# adcsd_shield.net
KiCad netlist of a schematic drawn in EAGLE
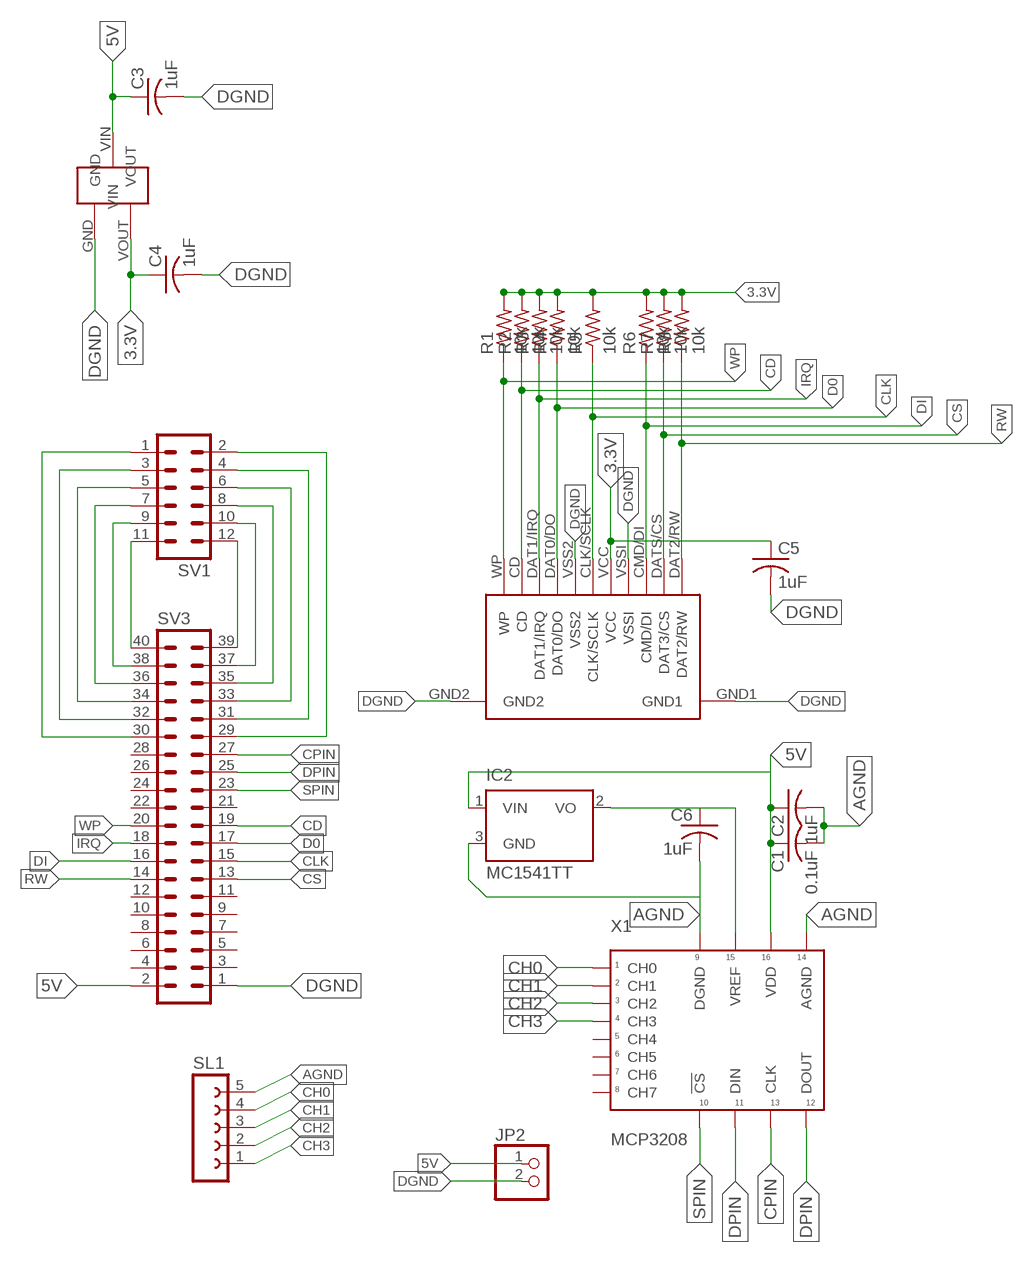
[diagram p0: schematic, sheet 1]

(export (version "E")
  (design (tool "Eeschema 10.0.6"))
  (components
    (comp (ref "C1")
      (value "0.1uF")
      (footprint "eagle-import:C0402")
      (libsource (lib "eagle-import") (part "C-USC0402"))
    )
    (comp (ref "C2")
      (value "1uF")
      (footprint "eagle-import:C0402")
      (libsource (lib "eagle-import") (part "C-USC0402"))
    )
    (comp (ref "C3")
      (value "1uF")
      (footprint "eagle-import:C0402")
      (libsource (lib "eagle-import") (part "C-USC0402"))
    )
    (comp (ref "C4")
      (value "1uF")
      (footprint "eagle-import:C0402")
      (libsource (lib "eagle-import") (part "C-USC0402"))
    )
    (comp (ref "C5")
      (value "1uF")
      (footprint "eagle-import:C0402")
      (libsource (lib "eagle-import") (part "C-USC0402"))
    )
    (comp (ref "C6")
      (value "1uF")
      (footprint "eagle-import:C0402")
      (libsource (lib "eagle-import") (part "C-USC0402"))
    )
    (comp (ref "IC2")
      (value "MC1541TT")
      (footprint "eagle-import:SOT23")
      (libsource (lib "eagle-import") (part "MC15TT41"))
    )
    (comp (ref "JP2")
      (value "PINHD-1X2")
      (footprint "eagle-import:1X02")
      (libsource (lib "eagle-import") (part "PINHD-1X2"))
    )
    (comp (ref "R1")
      (value "10k")
      (footprint "eagle-import:R0603")
      (libsource (lib "eagle-import") (part "R-US_R0603"))
    )
    (comp (ref "R2")
      (value "10k")
      (footprint "eagle-import:R0603")
      (libsource (lib "eagle-import") (part "R-US_R0603"))
    )
    (comp (ref "R3")
      (value "10k")
      (footprint "eagle-import:R0603")
      (libsource (lib "eagle-import") (part "R-US_R0603"))
    )
    (comp (ref "R4")
      (value "10k")
      (footprint "eagle-import:R0603")
      (libsource (lib "eagle-import") (part "R-US_R0603"))
    )
    (comp (ref "R5")
      (value "10k")
      (footprint "eagle-import:R0603")
      (libsource (lib "eagle-import") (part "R-US_R0603"))
    )
    (comp (ref "R6")
      (value "10k")
      (footprint "eagle-import:R0603")
      (libsource (lib "eagle-import") (part "R-US_R0603"))
    )
    (comp (ref "R7")
      (value "10k")
      (footprint "eagle-import:R0603")
      (libsource (lib "eagle-import") (part "R-US_R0603"))
    )
    (comp (ref "R8")
      (value "10k")
      (footprint "eagle-import:R0603")
      (libsource (lib "eagle-import") (part "R-US_R0603"))
    )
    (comp (ref "SL1")
      (value "FE05-1")
      (footprint "eagle-import:FE05-1")
      (libsource (lib "eagle-import") (part "FE05-1"))
    )
    (comp (ref "SV1")
      (value "MA06-2")
      (footprint "eagle-import:MA06-2")
      (libsource (lib "eagle-import") (part "MA06-2"))
    )
    (comp (ref "SV3")
      (value "MA20-2")
      (footprint "eagle-import:MA20-2")
      (libsource (lib "eagle-import") (part "MA20-2"))
    )
    (comp (ref "U$1")
      (value "SD_1.0")
      (footprint "eagle-import:SD_1.0")
      (libsource (lib "eagle-import") (part "SD_1.0"))
    )
    (comp (ref "U$2")
      (value "MCP1700T")
      (footprint "eagle-import:SOT23")
      (libsource (lib "eagle-import") (part "MCP1700T"))
    )
    (comp (ref "X1")
      (value "MCP3208")
      (footprint "eagle-import:DIP16")
      (libsource (lib "eagle-import") (part "21298EDIP"))
    )
  )
  (nets
    (net (code "1") (name "3.3V") (class "Default")
      (node (ref "C4") (pin "1") (pinfunction "1_1") (pintype "passive"))
      (node (ref "C5") (pin "1") (pinfunction "1_1") (pintype "passive"))
      (node (ref "R1") (pin "2") (pinfunction "2_2") (pintype "passive"))
      (node (ref "R2") (pin "2") (pinfunction "2_2") (pintype "passive"))
      (node (ref "R3") (pin "2") (pinfunction "2_2") (pintype "passive"))
      (node (ref "R4") (pin "2") (pinfunction "2_2") (pintype "passive"))
      (node (ref "R5") (pin "2") (pinfunction "2_2") (pintype "passive"))
      (node (ref "R6") (pin "2") (pinfunction "2_2") (pintype "passive"))
      (node (ref "R7") (pin "2") (pinfunction "2_2") (pintype "passive"))
      (node (ref "R8") (pin "2") (pinfunction "2_2") (pintype "passive"))
      (node (ref "U$1") (pin "VCC") (pinfunction "VCC_VCC") (pintype "bidirectional"))
      (node (ref "U$2") (pin "VOUT") (pinfunction "VOUT_VOUT") (pintype "bidirectional"))
    )
    (net (code "2") (name "5V") (class "Default")
      (node (ref "C1") (pin "1") (pinfunction "1_1") (pintype "passive"))
      (node (ref "C2") (pin "1") (pinfunction "1_1") (pintype "passive"))
      (node (ref "C3") (pin "1") (pinfunction "1_1") (pintype "passive"))
      (node (ref "IC2") (pin "1") (pinfunction "VIN_1") (pintype "input"))
      (node (ref "JP2") (pin "1") (pinfunction "1_1") (pintype "passive"))
      (node (ref "SV3") (pin "2") (pinfunction "2_2") (pintype "passive"))
      (node (ref "U$2") (pin "VIN") (pinfunction "VIN_VIN") (pintype "bidirectional"))
      (node (ref "X1") (pin "P$16") (pinfunction "VDD_P$16") (pintype "bidirectional"))
    )
    (net (code "3") (name "AGND") (class "Default")
      (node (ref "C1") (pin "2") (pinfunction "2_2") (pintype "passive"))
      (node (ref "C2") (pin "2") (pinfunction "2_2") (pintype "passive"))
      (node (ref "C6") (pin "2") (pinfunction "2_2") (pintype "passive"))
      (node (ref "IC2") (pin "3") (pinfunction "GND_3") (pintype "passive"))
      (node (ref "SL1") (pin "5") (pinfunction "5_5") (pintype "passive"))
      (node (ref "X1") (pin "P$14") (pinfunction "AGND_P$14") (pintype "bidirectional"))
      (node (ref "X1") (pin "P$9") (pinfunction "DGND_P$9") (pintype "bidirectional"))
    )
    (net (code "4") (name "CD") (class "Default")
      (node (ref "R2") (pin "1") (pinfunction "1_1") (pintype "passive"))
      (node (ref "SV3") (pin "19") (pinfunction "19_19") (pintype "passive"))
      (node (ref "U$1") (pin "CD") (pinfunction "CD_CD") (pintype "bidirectional"))
    )
    (net (code "5") (name "CH0") (class "Default")
      (node (ref "SL1") (pin "4") (pinfunction "4_4") (pintype "passive"))
      (node (ref "X1") (pin "P$1") (pinfunction "CH0_P$1") (pintype "bidirectional"))
    )
    (net (code "6") (name "CH1") (class "Default")
      (node (ref "SL1") (pin "3") (pinfunction "3_3") (pintype "passive"))
      (node (ref "X1") (pin "P$2") (pinfunction "CH1_P$2") (pintype "bidirectional"))
    )
    (net (code "7") (name "CH2") (class "Default")
      (node (ref "SL1") (pin "2") (pinfunction "2_2") (pintype "passive"))
      (node (ref "X1") (pin "P$3") (pinfunction "CH2_P$3") (pintype "bidirectional"))
    )
    (net (code "8") (name "CH3") (class "Default")
      (node (ref "SL1") (pin "1") (pinfunction "1_1") (pintype "passive"))
      (node (ref "X1") (pin "P$4") (pinfunction "CH3_P$4") (pintype "bidirectional"))
    )
    (net (code "9") (name "CLK") (class "Default")
      (node (ref "R5") (pin "1") (pinfunction "1_1") (pintype "passive"))
      (node (ref "SV3") (pin "15") (pinfunction "15_15") (pintype "passive"))
      (node (ref "U$1") (pin "CLK/SCLK") (pinfunction "CLK/SCLK_CLK/SCLK") (pintype "bidirectional"))
    )
    (net (code "10") (name "CPIN") (class "Default")
      (node (ref "SV3") (pin "27") (pinfunction "27_27") (pintype "passive"))
      (node (ref "X1") (pin "P$13") (pinfunction "CLK_P$13") (pintype "bidirectional"))
    )
    (net (code "11") (name "CS") (class "Default")
      (node (ref "R7") (pin "1") (pinfunction "1_1") (pintype "passive"))
      (node (ref "SV3") (pin "13") (pinfunction "13_13") (pintype "passive"))
      (node (ref "U$1") (pin "DATS/CS") (pinfunction "DAT3/CS_DATS/CS") (pintype "bidirectional"))
    )
    (net (code "12") (name "D0") (class "Default")
      (node (ref "R4") (pin "1") (pinfunction "1_1") (pintype "passive"))
      (node (ref "SV3") (pin "17") (pinfunction "17_17") (pintype "passive"))
      (node (ref "U$1") (pin "DAT0/DO") (pinfunction "DAT0/DO_DAT0/DO") (pintype "bidirectional"))
    )
    (net (code "13") (name "DGND") (class "Default")
      (node (ref "C3") (pin "2") (pinfunction "2_2") (pintype "passive"))
      (node (ref "C4") (pin "2") (pinfunction "2_2") (pintype "passive"))
      (node (ref "C5") (pin "2") (pinfunction "2_2") (pintype "passive"))
      (node (ref "JP2") (pin "2") (pinfunction "2_2") (pintype "passive"))
      (node (ref "SV3") (pin "1") (pinfunction "1_1") (pintype "passive"))
      (node (ref "U$1") (pin "GND1") (pinfunction "GND1_GND1") (pintype "bidirectional"))
      (node (ref "U$1") (pin "GND2") (pinfunction "GND2_GND2") (pintype "bidirectional"))
      (node (ref "U$1") (pin "VSS2") (pinfunction "VSS2_VSS2") (pintype "bidirectional"))
      (node (ref "U$1") (pin "VSSI") (pinfunction "VSSI_VSSI") (pintype "bidirectional"))
      (node (ref "U$2") (pin "GND") (pinfunction "GND_GND") (pintype "bidirectional"))
    )
    (net (code "14") (name "DI") (class "Default")
      (node (ref "R6") (pin "1") (pinfunction "1_1") (pintype "passive"))
      (node (ref "SV3") (pin "16") (pinfunction "16_16") (pintype "passive"))
      (node (ref "U$1") (pin "CMD/DI") (pinfunction "CMD/DI_CMD/DI") (pintype "bidirectional"))
    )
    (net (code "15") (name "DPIN") (class "Default")
      (node (ref "SV3") (pin "25") (pinfunction "25_25") (pintype "passive"))
      (node (ref "X1") (pin "P$11") (pinfunction "DIN_P$11") (pintype "bidirectional"))
      (node (ref "X1") (pin "P$12") (pinfunction "DOUT_P$12") (pintype "bidirectional"))
    )
    (net (code "16") (name "IRQ") (class "Default")
      (node (ref "R3") (pin "1") (pinfunction "1_1") (pintype "passive"))
      (node (ref "SV3") (pin "18") (pinfunction "18_18") (pintype "passive"))
      (node (ref "U$1") (pin "DAT1/IRQ") (pinfunction "DAT1/IRQ_DAT1/IRQ") (pintype "bidirectional"))
    )
    (net (code "17") (name "Net-(IC2-VO)") (class "Default")
      (node (ref "C6") (pin "1") (pinfunction "1_1") (pintype "passive"))
      (node (ref "IC2") (pin "2") (pinfunction "VO_2") (pintype "output"))
      (node (ref "X1") (pin "P$15") (pinfunction "VREF_P$15") (pintype "bidirectional"))
    )
    (net (code "18") (name "Net-(SV1-Pad1)") (class "Default")
      (node (ref "SV1") (pin "1") (pinfunction "1_1") (pintype "passive"))
      (node (ref "SV3") (pin "30") (pinfunction "30_30") (pintype "passive"))
    )
    (net (code "19") (name "Net-(SV1-Pad2)") (class "Default")
      (node (ref "SV1") (pin "2") (pinfunction "2_2") (pintype "passive"))
      (node (ref "SV3") (pin "29") (pinfunction "29_29") (pintype "passive"))
    )
    (net (code "20") (name "Net-(SV1-Pad3)") (class "Default")
      (node (ref "SV1") (pin "3") (pinfunction "3_3") (pintype "passive"))
      (node (ref "SV3") (pin "32") (pinfunction "32_32") (pintype "passive"))
    )
    (net (code "21") (name "Net-(SV1-Pad4)") (class "Default")
      (node (ref "SV1") (pin "4") (pinfunction "4_4") (pintype "passive"))
      (node (ref "SV3") (pin "31") (pinfunction "31_31") (pintype "passive"))
    )
    (net (code "22") (name "Net-(SV1-Pad5)") (class "Default")
      (node (ref "SV1") (pin "5") (pinfunction "5_5") (pintype "passive"))
      (node (ref "SV3") (pin "34") (pinfunction "34_34") (pintype "passive"))
    )
    (net (code "23") (name "Net-(SV1-Pad6)") (class "Default")
      (node (ref "SV1") (pin "6") (pinfunction "6_6") (pintype "passive"))
      (node (ref "SV3") (pin "33") (pinfunction "33_33") (pintype "passive"))
    )
    (net (code "24") (name "Net-(SV1-Pad7)") (class "Default")
      (node (ref "SV1") (pin "7") (pinfunction "7_7") (pintype "passive"))
      (node (ref "SV3") (pin "36") (pinfunction "36_36") (pintype "passive"))
    )
    (net (code "25") (name "Net-(SV1-Pad8)") (class "Default")
      (node (ref "SV1") (pin "8") (pinfunction "8_8") (pintype "passive"))
      (node (ref "SV3") (pin "35") (pinfunction "35_35") (pintype "passive"))
    )
    (net (code "26") (name "Net-(SV1-Pad9)") (class "Default")
      (node (ref "SV1") (pin "9") (pinfunction "9_9") (pintype "passive"))
      (node (ref "SV3") (pin "38") (pinfunction "38_38") (pintype "passive"))
    )
    (net (code "27") (name "Net-(SV1-Pad10)") (class "Default")
      (node (ref "SV1") (pin "10") (pinfunction "10_10") (pintype "passive"))
      (node (ref "SV3") (pin "37") (pinfunction "37_37") (pintype "passive"))
    )
    (net (code "28") (name "Net-(SV1-Pad11)") (class "Default")
      (node (ref "SV1") (pin "11") (pinfunction "11_11") (pintype "passive"))
      (node (ref "SV3") (pin "40") (pinfunction "40_40") (pintype "passive"))
    )
    (net (code "29") (name "Net-(SV1-Pad12)") (class "Default")
      (node (ref "SV1") (pin "12") (pinfunction "12_12") (pintype "passive"))
      (node (ref "SV3") (pin "39") (pinfunction "39_39") (pintype "passive"))
    )
    (net (code "30") (name "RW") (class "Default")
      (node (ref "R8") (pin "1") (pinfunction "1_1") (pintype "passive"))
      (node (ref "SV3") (pin "14") (pinfunction "14_14") (pintype "passive"))
      (node (ref "U$1") (pin "DAT2/RW") (pinfunction "DAT2/RW_DAT2/RW") (pintype "bidirectional"))
    )
    (net (code "31") (name "SPIN") (class "Default")
      (node (ref "SV3") (pin "23") (pinfunction "23_23") (pintype "passive"))
      (node (ref "X1") (pin "P$10") (pinfunction "~{CS}_P$10") (pintype "bidirectional"))
    )
    (net (code "32") (name "WP") (class "Default")
      (node (ref "R1") (pin "1") (pinfunction "1_1") (pintype "passive"))
      (node (ref "SV3") (pin "20") (pinfunction "20_20") (pintype "passive"))
      (node (ref "U$1") (pin "WP") (pinfunction "WP_WP") (pintype "bidirectional"))
    )
    (net (code "33") (name "unconnected-(SV3-Pad3)") (class "Default")
      (node (ref "SV3") (pin "3") (pinfunction "3_3") (pintype "passive"))
    )
    (net (code "34") (name "unconnected-(SV3-Pad4)") (class "Default")
      (node (ref "SV3") (pin "4") (pinfunction "4_4") (pintype "passive"))
    )
    (net (code "35") (name "unconnected-(SV3-Pad5)") (class "Default")
      (node (ref "SV3") (pin "5") (pinfunction "5_5") (pintype "passive"))
    )
    (net (code "36") (name "unconnected-(SV3-Pad6)") (class "Default")
      (node (ref "SV3") (pin "6") (pinfunction "6_6") (pintype "passive"))
    )
    (net (code "37") (name "unconnected-(SV3-Pad7)") (class "Default")
      (node (ref "SV3") (pin "7") (pinfunction "7_7") (pintype "passive"))
    )
    (net (code "38") (name "unconnected-(SV3-Pad8)") (class "Default")
      (node (ref "SV3") (pin "8") (pinfunction "8_8") (pintype "passive"))
    )
    (net (code "39") (name "unconnected-(SV3-Pad9)") (class "Default")
      (node (ref "SV3") (pin "9") (pinfunction "9_9") (pintype "passive"))
    )
    (net (code "40") (name "unconnected-(SV3-Pad10)") (class "Default")
      (node (ref "SV3") (pin "10") (pinfunction "10_10") (pintype "passive"))
    )
    (net (code "41") (name "unconnected-(SV3-Pad11)") (class "Default")
      (node (ref "SV3") (pin "11") (pinfunction "11_11") (pintype "passive"))
    )
    (net (code "42") (name "unconnected-(SV3-Pad12)") (class "Default")
      (node (ref "SV3") (pin "12") (pinfunction "12_12") (pintype "passive"))
    )
    (net (code "43") (name "unconnected-(SV3-Pad21)") (class "Default")
      (node (ref "SV3") (pin "21") (pinfunction "21_21") (pintype "passive"))
    )
    (net (code "44") (name "unconnected-(SV3-Pad22)") (class "Default")
      (node (ref "SV3") (pin "22") (pinfunction "22_22") (pintype "passive"))
    )
    (net (code "45") (name "unconnected-(SV3-Pad24)") (class "Default")
      (node (ref "SV3") (pin "24") (pinfunction "24_24") (pintype "passive"))
    )
    (net (code "46") (name "unconnected-(SV3-Pad26)") (class "Default")
      (node (ref "SV3") (pin "26") (pinfunction "26_26") (pintype "passive"))
    )
    (net (code "47") (name "unconnected-(SV3-Pad28)") (class "Default")
      (node (ref "SV3") (pin "28") (pinfunction "28_28") (pintype "passive"))
    )
    (net (code "48") (name "unconnected-(X1-CH4-PadP$5)") (class "Default")
      (node (ref "X1") (pin "P$5") (pinfunction "CH4_P$5") (pintype "bidirectional"))
    )
    (net (code "49") (name "unconnected-(X1-CH5-PadP$6)") (class "Default")
      (node (ref "X1") (pin "P$6") (pinfunction "CH5_P$6") (pintype "bidirectional"))
    )
    (net (code "50") (name "unconnected-(X1-CH6-PadP$7)") (class "Default")
      (node (ref "X1") (pin "P$7") (pinfunction "CH6_P$7") (pintype "bidirectional"))
    )
    (net (code "51") (name "unconnected-(X1-CH7-PadP$8)") (class "Default")
      (node (ref "X1") (pin "P$8") (pinfunction "CH7_P$8") (pintype "bidirectional"))
    )
  )
)
